# EBN_Sensors_V02.net
KiCad netlist of a schematic drawn in EAGLE
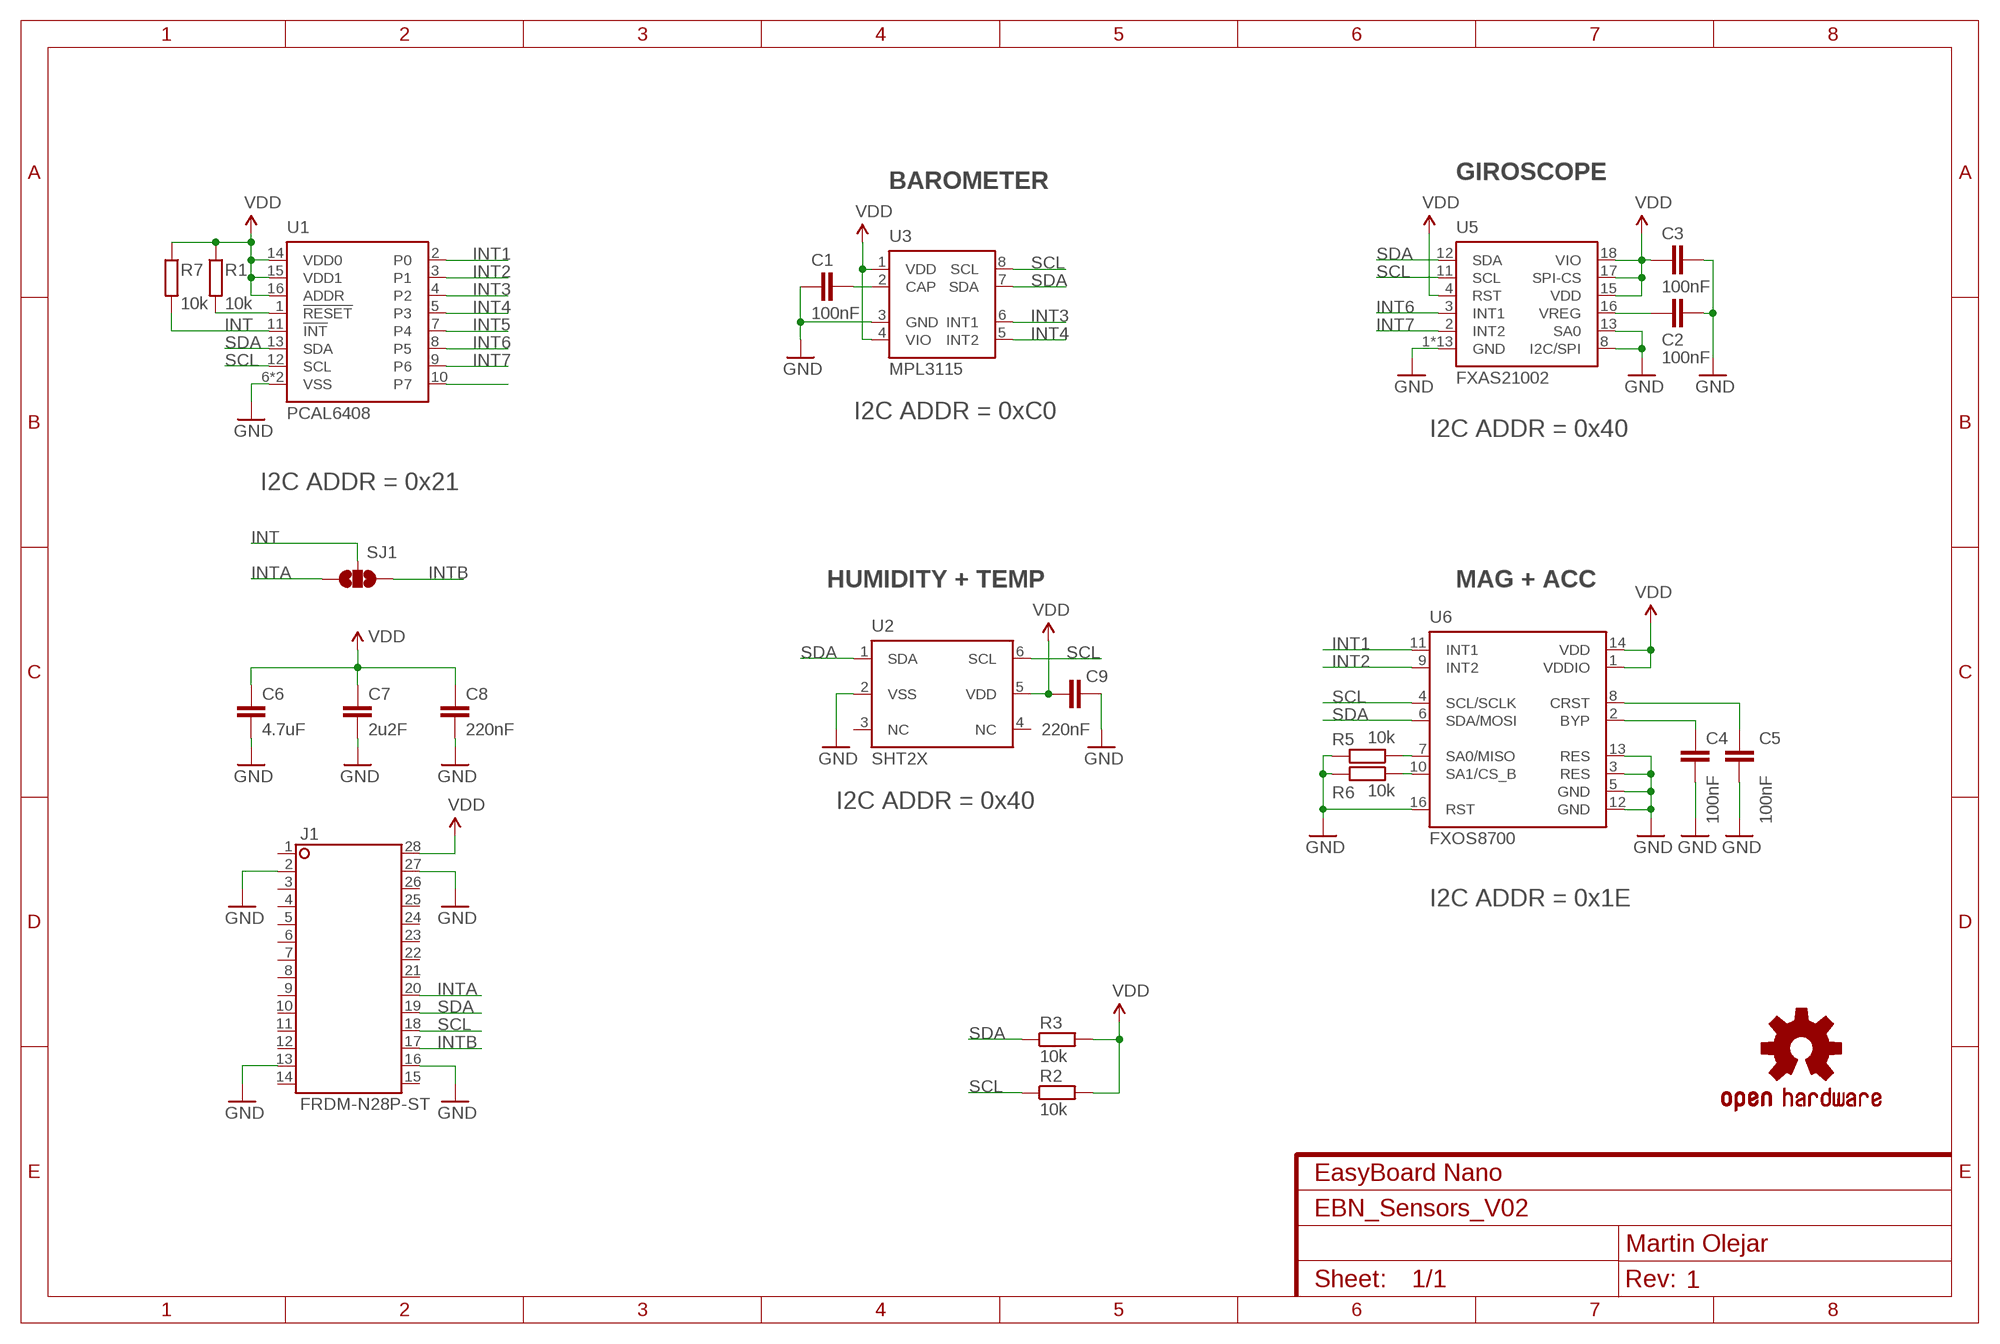
[diagram p0: schematic, sheet 1]

(export (version "E")
  (design (tool "Eeschema 10.0.6"))
  (components
    (comp (ref "C1")
      (value "100nF")
      (footprint "eagle-import:C0402")
      (libsource (lib "eagle-import") (part "C-EUC0402"))
    )
    (comp (ref "C2")
      (value "100nF")
      (footprint "eagle-import:C0402")
      (libsource (lib "eagle-import") (part "C-EUC0402"))
    )
    (comp (ref "C3")
      (value "100nF")
      (footprint "eagle-import:C0402")
      (libsource (lib "eagle-import") (part "C-EUC0402"))
    )
    (comp (ref "C4")
      (value "100nF")
      (footprint "eagle-import:C0402")
      (libsource (lib "eagle-import") (part "C-EUC0402"))
    )
    (comp (ref "C5")
      (value "100nF")
      (footprint "eagle-import:C0402")
      (libsource (lib "eagle-import") (part "C-EUC0402"))
    )
    (comp (ref "C6")
      (value "4.7uF")
      (footprint "eagle-import:C0603")
      (libsource (lib "eagle-import") (part "C-EUC0603"))
    )
    (comp (ref "C7")
      (value "2u2F")
      (footprint "eagle-import:C0603")
      (libsource (lib "eagle-import") (part "C-EUC0603"))
    )
    (comp (ref "C8")
      (value "220nF")
      (footprint "eagle-import:C0402")
      (libsource (lib "eagle-import") (part "C-EUC0402"))
    )
    (comp (ref "C9")
      (value "220nF")
      (footprint "eagle-import:C0402")
      (libsource (lib "eagle-import") (part "C-EUC0402"))
    )
    (comp (ref "J1")
      (value "FRDM-N28P-ST")
      (footprint "eagle-import:FRDM-N28P-SHIELD")
      (libsource (lib "eagle-import") (part "FRDM-N28P-ST"))
    )
    (comp (ref "LOGO1")
      (value "OSHW-LOGOS")
      (footprint "eagle-import:OSHW-LOGO-S")
      (libsource (lib "eagle-import") (part "OSHW-LOGOS"))
    )
    (comp (ref "R1")
      (value "10k")
      (footprint "eagle-import:R0402")
      (libsource (lib "eagle-import") (part "R-EUR0402"))
    )
    (comp (ref "R2")
      (value "10k")
      (footprint "eagle-import:R0402")
      (libsource (lib "eagle-import") (part "R-EUR0402"))
    )
    (comp (ref "R3")
      (value "10k")
      (footprint "eagle-import:R0402")
      (libsource (lib "eagle-import") (part "R-EUR0402"))
    )
    (comp (ref "R5")
      (value "10k")
      (footprint "eagle-import:R0402")
      (libsource (lib "eagle-import") (part "R-EUR0402"))
    )
    (comp (ref "R6")
      (value "10k")
      (footprint "eagle-import:R0402")
      (libsource (lib "eagle-import") (part "R-EUR0402"))
    )
    (comp (ref "R7")
      (value "10k")
      (footprint "eagle-import:R0402")
      (libsource (lib "eagle-import") (part "R-EUR0402"))
    )
    (comp (ref "SJ1")
      (value "SJ2W-S")
      (footprint "eagle-import:JUMPER-SMD-S2X")
      (libsource (lib "eagle-import") (part "SJ2W-S"))
    )
    (comp (ref "U1")
      (value "PCAL6408")
      (footprint "eagle-import:QFN16-3X3MM")
      (libsource (lib "eagle-import") (part "PCAL6408"))
    )
    (comp (ref "U2")
      (value "SHT2X")
      (footprint "eagle-import:DFN6_3X3")
      (libsource (lib "eagle-import") (part "SHT2X"))
    )
    (comp (ref "U3")
      (value "MPL3115")
      (footprint "eagle-import:LGA-8")
      (libsource (lib "eagle-import") (part "MPL3115"))
    )
    (comp (ref "U5")
      (value "FXAS21002")
      (footprint "eagle-import:QFN24")
      (libsource (lib "eagle-import") (part "FXAS21002"))
    )
    (comp (ref "U6")
      (value "FXOS8700")
      (footprint "eagle-import:QFN16-FX")
      (libsource (lib "eagle-import") (part "FXOS8700"))
    )
  )
  (nets
    (net (code "1") (name "/INT") (class "Default")
      (node (ref "R7") (pin "2") (pinfunction "2_2") (pintype "passive"))
      (node (ref "SJ1") (pin "2") (pinfunction "2_2") (pintype "passive"))
      (node (ref "U1") (pin "11") (pinfunction "~{INT}_11") (pintype "output"))
    )
    (net (code "2") (name "/INT1") (class "Default")
      (node (ref "U1") (pin "2") (pinfunction "P0_2") (pintype "bidirectional"))
      (node (ref "U6") (pin "11") (pinfunction "INT1_11") (pintype "output"))
    )
    (net (code "3") (name "/INT2") (class "Default")
      (node (ref "U1") (pin "3") (pinfunction "P1_3") (pintype "bidirectional"))
      (node (ref "U6") (pin "9") (pinfunction "INT2_9") (pintype "output"))
    )
    (net (code "4") (name "/INT3") (class "Default")
      (node (ref "U1") (pin "4") (pinfunction "P2_4") (pintype "bidirectional"))
      (node (ref "U3") (pin "6") (pinfunction "INT1_6") (pintype "output"))
    )
    (net (code "5") (name "/INT4") (class "Default")
      (node (ref "U1") (pin "5") (pinfunction "P3_5") (pintype "bidirectional"))
      (node (ref "U3") (pin "5") (pinfunction "INT2_5") (pintype "output"))
    )
    (net (code "6") (name "/INT5") (class "Default")
      (node (ref "U1") (pin "7") (pinfunction "P4_7") (pintype "bidirectional"))
    )
    (net (code "7") (name "/INT6") (class "Default")
      (node (ref "U1") (pin "8") (pinfunction "P5_8") (pintype "bidirectional"))
      (node (ref "U5") (pin "3") (pinfunction "INT1_3") (pintype "output"))
    )
    (net (code "8") (name "/INT7") (class "Default")
      (node (ref "U1") (pin "9") (pinfunction "P6_9") (pintype "bidirectional"))
      (node (ref "U5") (pin "2") (pinfunction "INT2_2") (pintype "output"))
    )
    (net (code "9") (name "/INTA") (class "Default")
      (node (ref "J1") (pin "20") (pinfunction "20_20") (pintype "passive"))
      (node (ref "SJ1") (pin "3") (pinfunction "3_3") (pintype "passive"))
    )
    (net (code "10") (name "/INTB") (class "Default")
      (node (ref "J1") (pin "17") (pinfunction "17_17") (pintype "passive"))
      (node (ref "SJ1") (pin "1") (pinfunction "1_1") (pintype "passive"))
    )
    (net (code "11") (name "/SCL") (class "Default")
      (node (ref "J1") (pin "18") (pinfunction "18_18") (pintype "passive"))
      (node (ref "R2") (pin "1") (pinfunction "1_1") (pintype "passive"))
      (node (ref "U1") (pin "12") (pinfunction "SCL_12") (pintype "bidirectional"))
      (node (ref "U2") (pin "6") (pinfunction "SCL_6") (pintype "bidirectional"))
      (node (ref "U3") (pin "8") (pinfunction "SCL_8") (pintype "bidirectional"))
      (node (ref "U5") (pin "11") (pinfunction "SCL_11") (pintype "bidirectional"))
      (node (ref "U6") (pin "4") (pinfunction "SCL/SCLK_4") (pintype "bidirectional"))
    )
    (net (code "12") (name "/SDA") (class "Default")
      (node (ref "J1") (pin "19") (pinfunction "19_19") (pintype "passive"))
      (node (ref "R3") (pin "1") (pinfunction "1_1") (pintype "passive"))
      (node (ref "U1") (pin "13") (pinfunction "SDA_13") (pintype "bidirectional"))
      (node (ref "U2") (pin "1") (pinfunction "SDA_1") (pintype "bidirectional"))
      (node (ref "U3") (pin "7") (pinfunction "SDA_7") (pintype "bidirectional"))
      (node (ref "U5") (pin "12") (pinfunction "SDA_12") (pintype "bidirectional"))
      (node (ref "U6") (pin "6") (pinfunction "SDA/MOSI_6") (pintype "bidirectional"))
    )
    (net (code "13") (name "GND") (class "Default")
      (node (ref "C1") (pin "1") (pinfunction "1_1") (pintype "passive"))
      (node (ref "C2") (pin "1") (pinfunction "1_1") (pintype "passive"))
      (node (ref "C3") (pin "1") (pinfunction "1_1") (pintype "passive"))
      (node (ref "C4") (pin "2") (pinfunction "2_2") (pintype "passive"))
      (node (ref "C5") (pin "2") (pinfunction "2_2") (pintype "passive"))
      (node (ref "C6") (pin "2") (pinfunction "2_2") (pintype "passive"))
      (node (ref "C7") (pin "2") (pinfunction "2_2") (pintype "passive"))
      (node (ref "C8") (pin "2") (pinfunction "2_2") (pintype "passive"))
      (node (ref "C9") (pin "1") (pinfunction "1_1") (pintype "passive"))
      (node (ref "J1") (pin "13") (pinfunction "13_13") (pintype "passive"))
      (node (ref "J1") (pin "16") (pinfunction "16_16") (pintype "passive"))
      (node (ref "J1") (pin "2") (pinfunction "2_2") (pintype "passive"))
      (node (ref "J1") (pin "27") (pinfunction "27_27") (pintype "passive"))
      (node (ref "R5") (pin "2") (pinfunction "2_2") (pintype "passive"))
      (node (ref "R6") (pin "2") (pinfunction "2_2") (pintype "passive"))
      (node (ref "U1") (pin "6") (pinfunction "VSS_6") (pintype "power_in"))
      (node (ref "U1") (pin "EXT") (pinfunction "VSS_EXT") (pintype "power_in"))
      (node (ref "U2") (pin "2") (pinfunction "VSS_2") (pintype "power_in"))
      (node (ref "U3") (pin "3") (pinfunction "GND_3") (pintype "power_in"))
      (node (ref "U5") (pin "1") (pinfunction "GND_1") (pintype "power_in"))
      (node (ref "U5") (pin "10") (pinfunction "GND_10") (pintype "power_in"))
      (node (ref "U5") (pin "13") (pinfunction "SA0_13") (pintype "input"))
      (node (ref "U5") (pin "14") (pinfunction "GND_14") (pintype "power_in"))
      (node (ref "U5") (pin "19") (pinfunction "GND_19") (pintype "power_in"))
      (node (ref "U5") (pin "20") (pinfunction "GND_20") (pintype "power_in"))
      (node (ref "U5") (pin "21") (pinfunction "GND_21") (pintype "power_in"))
      (node (ref "U5") (pin "22") (pinfunction "GND_22") (pintype "power_in"))
      (node (ref "U5") (pin "23") (pinfunction "GND_23") (pintype "power_in"))
      (node (ref "U5") (pin "24") (pinfunction "GND_24") (pintype "power_in"))
      (node (ref "U5") (pin "5") (pinfunction "GND_5") (pintype "power_in"))
      (node (ref "U5") (pin "6") (pinfunction "GND_6") (pintype "power_in"))
      (node (ref "U5") (pin "7") (pinfunction "GND_7") (pintype "power_in"))
      (node (ref "U5") (pin "8") (pinfunction "I2C/SPI_8") (pintype "input"))
      (node (ref "U5") (pin "9") (pinfunction "GND_9") (pintype "power_in"))
      (node (ref "U6") (pin "12") (pinfunction "GND_12") (pintype "power_in"))
      (node (ref "U6") (pin "13") (pinfunction "RES_13") (pintype "bidirectional"))
      (node (ref "U6") (pin "16") (pinfunction "RST_16") (pintype "input"))
      (node (ref "U6") (pin "3") (pinfunction "RES_3") (pintype "passive"))
      (node (ref "U6") (pin "5") (pinfunction "GND_5") (pintype "power_in"))
    )
    (net (code "14") (name "Net-(U1-~{RESET})") (class "Default")
      (node (ref "R1") (pin "2") (pinfunction "2_2") (pintype "passive"))
      (node (ref "U1") (pin "1") (pinfunction "~{RESET}_1") (pintype "input"))
    )
    (net (code "15") (name "Net-(U3-CAP)") (class "Default")
      (node (ref "C1") (pin "2") (pinfunction "2_2") (pintype "passive"))
      (node (ref "U3") (pin "2") (pinfunction "CAP_2") (pintype "power_in"))
    )
    (net (code "16") (name "Net-(U5-VREG)") (class "Default")
      (node (ref "C2") (pin "2") (pinfunction "2_2") (pintype "passive"))
      (node (ref "U5") (pin "16") (pinfunction "VREG_16") (pintype "power_in"))
    )
    (net (code "17") (name "Net-(U6-BYP)") (class "Default")
      (node (ref "C4") (pin "1") (pinfunction "1_1") (pintype "passive"))
      (node (ref "U6") (pin "2") (pinfunction "BYP_2") (pintype "passive"))
    )
    (net (code "18") (name "Net-(U6-CRST)") (class "Default")
      (node (ref "C5") (pin "1") (pinfunction "1_1") (pintype "passive"))
      (node (ref "U6") (pin "8") (pinfunction "CRST_8") (pintype "passive"))
    )
    (net (code "19") (name "Net-(U6-SA0{slash}MISO)") (class "Default")
      (node (ref "R5") (pin "1") (pinfunction "1_1") (pintype "passive"))
      (node (ref "U6") (pin "7") (pinfunction "SA0/MISO_7") (pintype "bidirectional"))
    )
    (net (code "20") (name "Net-(U6-SA1{slash}CS_B)") (class "Default")
      (node (ref "R6") (pin "1") (pinfunction "1_1") (pintype "passive"))
      (node (ref "U6") (pin "10") (pinfunction "SA1/CS_B_10") (pintype "bidirectional"))
    )
    (net (code "21") (name "VDD") (class "Default")
      (node (ref "C3") (pin "2") (pinfunction "2_2") (pintype "passive"))
      (node (ref "C6") (pin "1") (pinfunction "1_1") (pintype "passive"))
      (node (ref "C7") (pin "1") (pinfunction "1_1") (pintype "passive"))
      (node (ref "C8") (pin "1") (pinfunction "1_1") (pintype "passive"))
      (node (ref "C9") (pin "2") (pinfunction "2_2") (pintype "passive"))
      (node (ref "J1") (pin "28") (pinfunction "28_28") (pintype "passive"))
      (node (ref "R1") (pin "1") (pinfunction "1_1") (pintype "passive"))
      (node (ref "R2") (pin "2") (pinfunction "2_2") (pintype "passive"))
      (node (ref "R3") (pin "2") (pinfunction "2_2") (pintype "passive"))
      (node (ref "R7") (pin "1") (pinfunction "1_1") (pintype "passive"))
      (node (ref "U1") (pin "14") (pinfunction "VDD0_14") (pintype "power_in"))
      (node (ref "U1") (pin "15") (pinfunction "VDD1_15") (pintype "power_in"))
      (node (ref "U1") (pin "16") (pinfunction "ADDR_16") (pintype "input"))
      (node (ref "U2") (pin "5") (pinfunction "VDD_5") (pintype "power_in"))
      (node (ref "U3") (pin "1") (pinfunction "VDD_1") (pintype "power_in"))
      (node (ref "U3") (pin "4") (pinfunction "VIO_4") (pintype "input"))
      (node (ref "U5") (pin "15") (pinfunction "VDD_15") (pintype "power_in"))
      (node (ref "U5") (pin "17") (pinfunction "SPI-CS_17") (pintype "bidirectional"))
      (node (ref "U5") (pin "18") (pinfunction "VIO_18") (pintype "power_in"))
      (node (ref "U5") (pin "4") (pinfunction "RST_4") (pintype "input"))
      (node (ref "U6") (pin "1") (pinfunction "VDDIO_1") (pintype "power_in"))
      (node (ref "U6") (pin "14") (pinfunction "VDD_14") (pintype "power_in"))
    )
    (net (code "22") (name "unconnected-(J1-Pad1)") (class "Default")
      (node (ref "J1") (pin "1") (pinfunction "1_1") (pintype "passive"))
    )
    (net (code "23") (name "unconnected-(J1-Pad3)") (class "Default")
      (node (ref "J1") (pin "3") (pinfunction "3_3") (pintype "passive"))
    )
    (net (code "24") (name "unconnected-(J1-Pad4)") (class "Default")
      (node (ref "J1") (pin "4") (pinfunction "4_4") (pintype "passive"))
    )
    (net (code "25") (name "unconnected-(J1-Pad5)") (class "Default")
      (node (ref "J1") (pin "5") (pinfunction "5_5") (pintype "passive"))
    )
    (net (code "26") (name "unconnected-(J1-Pad6)") (class "Default")
      (node (ref "J1") (pin "6") (pinfunction "6_6") (pintype "passive"))
    )
    (net (code "27") (name "unconnected-(J1-Pad7)") (class "Default")
      (node (ref "J1") (pin "7") (pinfunction "7_7") (pintype "passive"))
    )
    (net (code "28") (name "unconnected-(J1-Pad8)") (class "Default")
      (node (ref "J1") (pin "8") (pinfunction "8_8") (pintype "passive"))
    )
    (net (code "29") (name "unconnected-(J1-Pad9)") (class "Default")
      (node (ref "J1") (pin "9") (pinfunction "9_9") (pintype "passive"))
    )
    (net (code "30") (name "unconnected-(J1-Pad10)") (class "Default")
      (node (ref "J1") (pin "10") (pinfunction "10_10") (pintype "passive"))
    )
    (net (code "31") (name "unconnected-(J1-Pad11)") (class "Default")
      (node (ref "J1") (pin "11") (pinfunction "11_11") (pintype "passive"))
    )
    (net (code "32") (name "unconnected-(J1-Pad12)") (class "Default")
      (node (ref "J1") (pin "12") (pinfunction "12_12") (pintype "passive"))
    )
    (net (code "33") (name "unconnected-(J1-Pad14)") (class "Default")
      (node (ref "J1") (pin "14") (pinfunction "14_14") (pintype "passive"))
    )
    (net (code "34") (name "unconnected-(J1-Pad15)") (class "Default")
      (node (ref "J1") (pin "15") (pinfunction "15_15") (pintype "passive"))
    )
    (net (code "35") (name "unconnected-(J1-Pad21)") (class "Default")
      (node (ref "J1") (pin "21") (pinfunction "21_21") (pintype "passive"))
    )
    (net (code "36") (name "unconnected-(J1-Pad22)") (class "Default")
      (node (ref "J1") (pin "22") (pinfunction "22_22") (pintype "passive"))
    )
    (net (code "37") (name "unconnected-(J1-Pad23)") (class "Default")
      (node (ref "J1") (pin "23") (pinfunction "23_23") (pintype "passive"))
    )
    (net (code "38") (name "unconnected-(J1-Pad24)") (class "Default")
      (node (ref "J1") (pin "24") (pinfunction "24_24") (pintype "passive"))
    )
    (net (code "39") (name "unconnected-(J1-Pad25)") (class "Default")
      (node (ref "J1") (pin "25") (pinfunction "25_25") (pintype "passive"))
    )
    (net (code "40") (name "unconnected-(J1-Pad26)") (class "Default")
      (node (ref "J1") (pin "26") (pinfunction "26_26") (pintype "passive"))
    )
    (net (code "41") (name "unconnected-(U1-P7-Pad10)") (class "Default")
      (node (ref "U1") (pin "10") (pinfunction "P7_10") (pintype "bidirectional"))
    )
    (net (code "42") (name "unconnected-(U2-NC-Pad3)") (class "Default")
      (node (ref "U2") (pin "3") (pinfunction "NC_3") (pintype "no_connect"))
    )
    (net (code "43") (name "unconnected-(U2-NC-Pad4)") (class "Default")
      (node (ref "U2") (pin "4") (pinfunction "NC_4") (pintype "no_connect"))
    )
  )
)
